# PCB.net
KiCad netlist of a schematic drawn in EAGLE
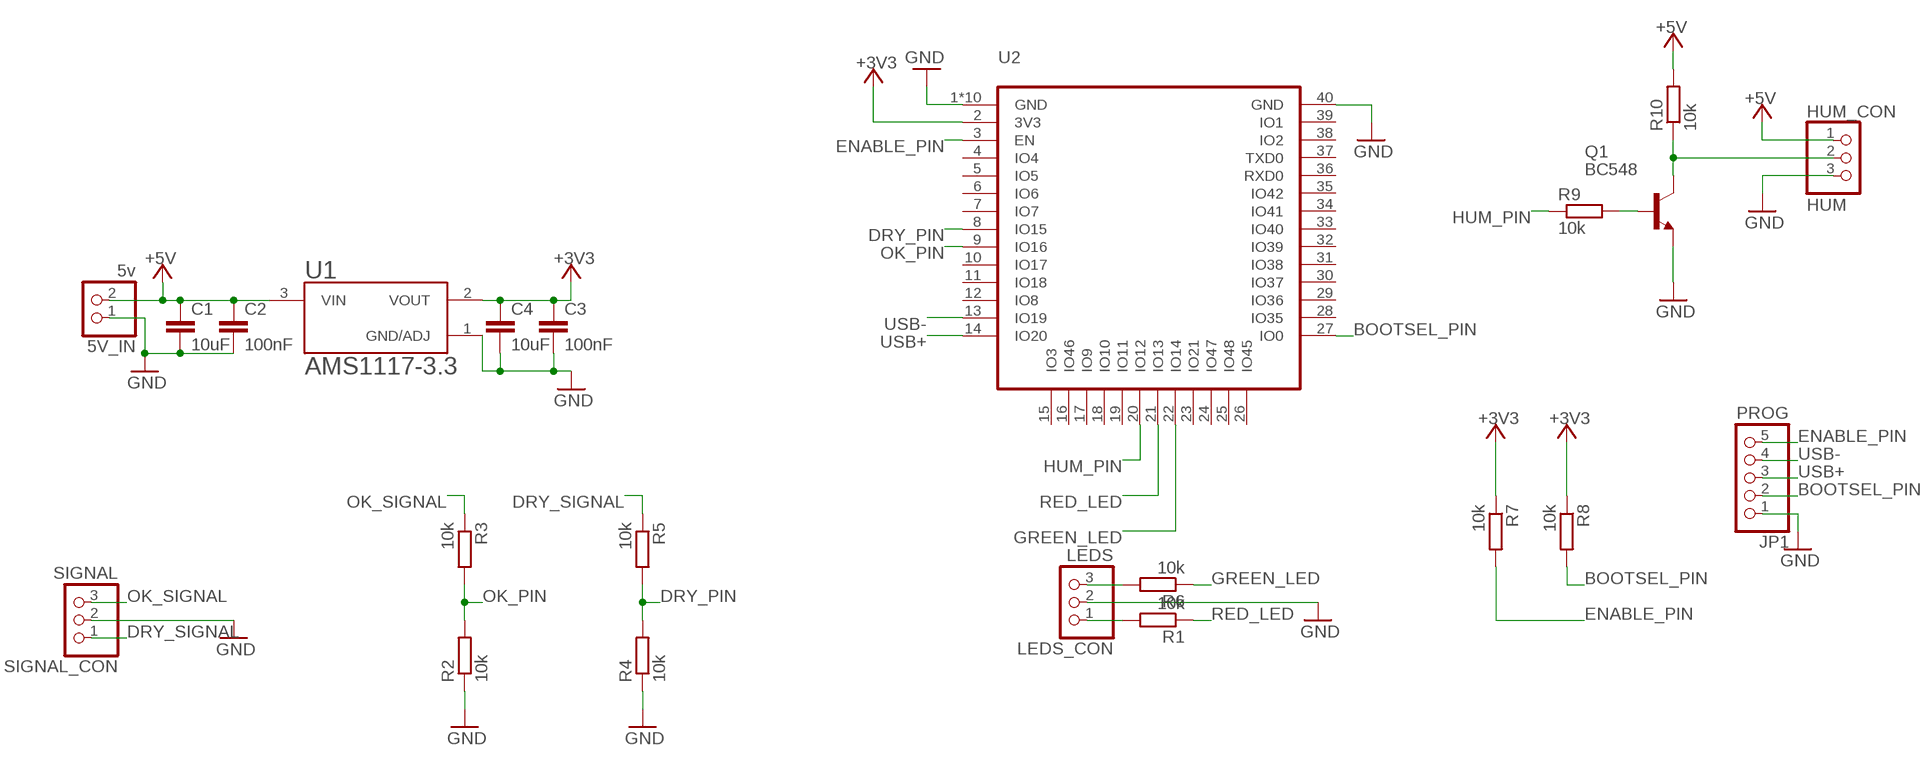
[diagram p0: schematic, sheet 1]

(export (version "E")
  (design (tool "Eeschema 10.0.6"))
  (components
    (comp (ref "5V_IN")
      (value "5v")
      (footprint "eagle-import:1X02")
      (libsource (lib "eagle-import") (part "PINHD-1X2"))
    )
    (comp (ref "C1")
      (value "10uF")
      (footprint "eagle-import:C1206")
      (libsource (lib "eagle-import") (part "C-EUC1206"))
    )
    (comp (ref "C2")
      (value "100nF")
      (footprint "eagle-import:C1206")
      (libsource (lib "eagle-import") (part "C-EUC1206"))
    )
    (comp (ref "C3")
      (value "100nF")
      (footprint "eagle-import:C1206")
      (libsource (lib "eagle-import") (part "C-EUC1206"))
    )
    (comp (ref "C4")
      (value "10uF")
      (footprint "eagle-import:C1206")
      (libsource (lib "eagle-import") (part "C-EUC1206"))
    )
    (comp (ref "HUM_CON")
      (value "HUM")
      (footprint "eagle-import:1X03")
      (libsource (lib "eagle-import") (part "PINHD-1X3"))
    )
    (comp (ref "JP1")
      (value "PROG")
      (footprint "eagle-import:1X05")
      (libsource (lib "eagle-import") (part "PINHD-1X5"))
    )
    (comp (ref "LEDS_CON")
      (value "LEDS")
      (footprint "eagle-import:1X03")
      (libsource (lib "eagle-import") (part "PINHD-1X3"))
    )
    (comp (ref "Q1")
      (value "BC548")
      (footprint "eagle-import:TO92-EBC")
      (libsource (lib "eagle-import") (part "BC548"))
    )
    (comp (ref "R1")
      (value "10k")
      (footprint "eagle-import:R1206")
      (libsource (lib "eagle-import") (part "R-EU_R1206"))
    )
    (comp (ref "R2")
      (value "10k")
      (footprint "eagle-import:R1206")
      (libsource (lib "eagle-import") (part "R-EU_R1206"))
    )
    (comp (ref "R3")
      (value "10k")
      (footprint "eagle-import:R1206")
      (libsource (lib "eagle-import") (part "R-EU_R1206"))
    )
    (comp (ref "R4")
      (value "10k")
      (footprint "eagle-import:R1206")
      (libsource (lib "eagle-import") (part "R-EU_R1206"))
    )
    (comp (ref "R5")
      (value "10k")
      (footprint "eagle-import:R1206")
      (libsource (lib "eagle-import") (part "R-EU_R1206"))
    )
    (comp (ref "R6")
      (value "10k")
      (footprint "eagle-import:R1206")
      (libsource (lib "eagle-import") (part "R-EU_R1206"))
    )
    (comp (ref "R7")
      (value "10k")
      (footprint "eagle-import:R1206")
      (libsource (lib "eagle-import") (part "R-EU_R1206"))
    )
    (comp (ref "R8")
      (value "10k")
      (footprint "eagle-import:R1206")
      (libsource (lib "eagle-import") (part "R-EU_R1206"))
    )
    (comp (ref "R9")
      (value "10k")
      (footprint "eagle-import:R1206")
      (libsource (lib "eagle-import") (part "R-EU_R1206"))
    )
    (comp (ref "R10")
      (value "10k")
      (footprint "eagle-import:R1206")
      (libsource (lib "eagle-import") (part "R-EU_R1206"))
    )
    (comp (ref "SIGNAL_CON")
      (value "SIGNAL")
      (footprint "eagle-import:1X03")
      (libsource (lib "eagle-import") (part "PINHD-1X3"))
    )
    (comp (ref "U1")
      (value "AMS1117-3.3")
      (footprint "eagle-import:SOT229P700X180-4N")
      (fields (field (name "MF") "Advanced Monolithic Systems"))
      (libsource (lib "eagle-import") (part "AMS1117-3.3"))
    )
    (comp (ref "U2")
      (value "ESP32-S3-WROOM-1")
      (footprint "eagle-import:ESP32-S3-WROOM-1")
      (fields (field (name "MF") "Espressif Systems"))
      (libsource (lib "eagle-import") (part "ESP32-S3-WROOM-1"))
    )
  )
  (nets
    (net (code "1") (name "+3V3") (class "Default")
      (node (ref "C3") (pin "1") (pinfunction "1_1") (pintype "passive"))
      (node (ref "C4") (pin "1") (pinfunction "1_1") (pintype "passive"))
      (node (ref "R7") (pin "1") (pinfunction "1_1") (pintype "passive"))
      (node (ref "R8") (pin "1") (pinfunction "1_1") (pintype "passive"))
      (node (ref "U1") (pin "2") (pinfunction "VOUT_2") (pintype "output"))
      (node (ref "U2") (pin "2") (pinfunction "3V3_2") (pintype "bidirectional"))
    )
    (net (code "2") (name "+5V") (class "Default")
      (node (ref "5V_IN") (pin "2") (pinfunction "2_2") (pintype "passive"))
      (node (ref "C1") (pin "1") (pinfunction "1_1") (pintype "passive"))
      (node (ref "C2") (pin "1") (pinfunction "1_1") (pintype "passive"))
      (node (ref "HUM_CON") (pin "1") (pinfunction "1_1") (pintype "passive"))
      (node (ref "R10") (pin "2") (pinfunction "2_2") (pintype "passive"))
      (node (ref "U1") (pin "3") (pinfunction "VIN_3") (pintype "input"))
    )
    (net (code "3") (name "/BOOTSEL_PIN") (class "Default")
      (node (ref "JP1") (pin "2") (pinfunction "2_2") (pintype "passive"))
      (node (ref "R8") (pin "2") (pinfunction "2_2") (pintype "passive"))
      (node (ref "U2") (pin "27") (pinfunction "IO0_27") (pintype "bidirectional"))
    )
    (net (code "4") (name "/DRY_PIN") (class "Default")
      (node (ref "R4") (pin "2") (pinfunction "2_2") (pintype "passive"))
      (node (ref "R5") (pin "2") (pinfunction "2_2") (pintype "passive"))
      (node (ref "U2") (pin "8") (pinfunction "IO15_8") (pintype "bidirectional"))
    )
    (net (code "5") (name "/DRY_SIGNAL") (class "Default")
      (node (ref "R5") (pin "1") (pinfunction "1_1") (pintype "passive"))
      (node (ref "SIGNAL_CON") (pin "1") (pinfunction "1_1") (pintype "passive"))
    )
    (net (code "6") (name "/ENABLE_PIN") (class "Default")
      (node (ref "JP1") (pin "5") (pinfunction "5_5") (pintype "passive"))
      (node (ref "R7") (pin "2") (pinfunction "2_2") (pintype "passive"))
      (node (ref "U2") (pin "3") (pinfunction "EN_3") (pintype "bidirectional"))
    )
    (net (code "7") (name "/GREEN_LED") (class "Default")
      (node (ref "R6") (pin "1") (pinfunction "1_1") (pintype "passive"))
      (node (ref "U2") (pin "22") (pinfunction "IO14_22") (pintype "bidirectional"))
    )
    (net (code "8") (name "/HUM_PIN") (class "Default")
      (node (ref "R9") (pin "1") (pinfunction "1_1") (pintype "passive"))
      (node (ref "U2") (pin "20") (pinfunction "IO12_20") (pintype "bidirectional"))
    )
    (net (code "9") (name "/OK_PIN") (class "Default")
      (node (ref "R2") (pin "2") (pinfunction "2_2") (pintype "passive"))
      (node (ref "R3") (pin "2") (pinfunction "2_2") (pintype "passive"))
      (node (ref "U2") (pin "9") (pinfunction "IO16_9") (pintype "bidirectional"))
    )
    (net (code "10") (name "/OK_SIGNAL") (class "Default")
      (node (ref "R3") (pin "1") (pinfunction "1_1") (pintype "passive"))
      (node (ref "SIGNAL_CON") (pin "3") (pinfunction "3_3") (pintype "passive"))
    )
    (net (code "11") (name "/RED_LED") (class "Default")
      (node (ref "R1") (pin "1") (pinfunction "1_1") (pintype "passive"))
      (node (ref "U2") (pin "21") (pinfunction "IO13_21") (pintype "bidirectional"))
    )
    (net (code "12") (name "/USB+") (class "Default")
      (node (ref "JP1") (pin "3") (pinfunction "3_3") (pintype "passive"))
      (node (ref "U2") (pin "14") (pinfunction "IO20_14") (pintype "bidirectional"))
    )
    (net (code "13") (name "/USB-") (class "Default")
      (node (ref "JP1") (pin "4") (pinfunction "4_4") (pintype "passive"))
      (node (ref "U2") (pin "13") (pinfunction "IO19_13") (pintype "bidirectional"))
    )
    (net (code "14") (name "GND") (class "Default")
      (node (ref "5V_IN") (pin "1") (pinfunction "1_1") (pintype "passive"))
      (node (ref "C1") (pin "2") (pinfunction "2_2") (pintype "passive"))
      (node (ref "C2") (pin "2") (pinfunction "2_2") (pintype "passive"))
      (node (ref "C3") (pin "2") (pinfunction "2_2") (pintype "passive"))
      (node (ref "C4") (pin "2") (pinfunction "2_2") (pintype "passive"))
      (node (ref "HUM_CON") (pin "3") (pinfunction "3_3") (pintype "passive"))
      (node (ref "JP1") (pin "1") (pinfunction "1_1") (pintype "passive"))
      (node (ref "LEDS_CON") (pin "2") (pinfunction "2_2") (pintype "passive"))
      (node (ref "Q1") (pin "E") (pinfunction "E_E") (pintype "passive"))
      (node (ref "R2") (pin "1") (pinfunction "1_1") (pintype "passive"))
      (node (ref "R4") (pin "1") (pinfunction "1_1") (pintype "passive"))
      (node (ref "SIGNAL_CON") (pin "2") (pinfunction "2_2") (pintype "passive"))
      (node (ref "U1") (pin "1") (pinfunction "GND/ADJ_1") (pintype "power_in"))
      (node (ref "U2") (pin "1") (pinfunction "GND_1") (pintype "bidirectional"))
      (node (ref "U2") (pin "40") (pinfunction "GND_40") (pintype "bidirectional"))
      (node (ref "U2") (pin "P$1") (pinfunction "GND_P$1") (pintype "bidirectional"))
      (node (ref "U2") (pin "P$2") (pinfunction "GND_P$2") (pintype "bidirectional"))
      (node (ref "U2") (pin "P$3") (pinfunction "GND_P$3") (pintype "bidirectional"))
      (node (ref "U2") (pin "P$4") (pinfunction "GND_P$4") (pintype "bidirectional"))
      (node (ref "U2") (pin "P$5") (pinfunction "GND_P$5") (pintype "bidirectional"))
      (node (ref "U2") (pin "P$6") (pinfunction "GND_P$6") (pintype "bidirectional"))
      (node (ref "U2") (pin "P$7") (pinfunction "GND_P$7") (pintype "bidirectional"))
      (node (ref "U2") (pin "P$8") (pinfunction "GND_P$8") (pintype "bidirectional"))
      (node (ref "U2") (pin "P$9") (pinfunction "GND_P$9") (pintype "bidirectional"))
    )
    (net (code "15") (name "Net-(HUM_CON-Pad2)") (class "Default")
      (node (ref "HUM_CON") (pin "2") (pinfunction "2_2") (pintype "passive"))
      (node (ref "Q1") (pin "C") (pinfunction "C_C") (pintype "passive"))
      (node (ref "R10") (pin "1") (pinfunction "1_1") (pintype "passive"))
    )
    (net (code "16") (name "Net-(LEDS_CON-Pad1)") (class "Default")
      (node (ref "LEDS_CON") (pin "1") (pinfunction "1_1") (pintype "passive"))
      (node (ref "R1") (pin "2") (pinfunction "2_2") (pintype "passive"))
    )
    (net (code "17") (name "Net-(LEDS_CON-Pad3)") (class "Default")
      (node (ref "LEDS_CON") (pin "3") (pinfunction "3_3") (pintype "passive"))
      (node (ref "R6") (pin "2") (pinfunction "2_2") (pintype "passive"))
    )
    (net (code "18") (name "Net-(Q1-PadB)") (class "Default")
      (node (ref "Q1") (pin "B") (pinfunction "B_B") (pintype "passive"))
      (node (ref "R9") (pin "2") (pinfunction "2_2") (pintype "passive"))
    )
    (net (code "19") (name "unconnected-(U2-IO1-Pad39)") (class "Default")
      (node (ref "U2") (pin "39") (pinfunction "IO1_39") (pintype "bidirectional"))
    )
    (net (code "20") (name "unconnected-(U2-IO2-Pad38)") (class "Default")
      (node (ref "U2") (pin "38") (pinfunction "IO2_38") (pintype "bidirectional"))
    )
    (net (code "21") (name "unconnected-(U2-IO3-Pad15)") (class "Default")
      (node (ref "U2") (pin "15") (pinfunction "IO3_15") (pintype "bidirectional"))
    )
    (net (code "22") (name "unconnected-(U2-IO4-Pad4)") (class "Default")
      (node (ref "U2") (pin "4") (pinfunction "IO4_4") (pintype "bidirectional"))
    )
    (net (code "23") (name "unconnected-(U2-IO5-Pad5)") (class "Default")
      (node (ref "U2") (pin "5") (pinfunction "IO5_5") (pintype "bidirectional"))
    )
    (net (code "24") (name "unconnected-(U2-IO6-Pad6)") (class "Default")
      (node (ref "U2") (pin "6") (pinfunction "IO6_6") (pintype "bidirectional"))
    )
    (net (code "25") (name "unconnected-(U2-IO7-Pad7)") (class "Default")
      (node (ref "U2") (pin "7") (pinfunction "IO7_7") (pintype "bidirectional"))
    )
    (net (code "26") (name "unconnected-(U2-IO8-Pad12)") (class "Default")
      (node (ref "U2") (pin "12") (pinfunction "IO8_12") (pintype "bidirectional"))
    )
    (net (code "27") (name "unconnected-(U2-IO9-Pad17)") (class "Default")
      (node (ref "U2") (pin "17") (pinfunction "IO9_17") (pintype "bidirectional"))
    )
    (net (code "28") (name "unconnected-(U2-IO10-Pad18)") (class "Default")
      (node (ref "U2") (pin "18") (pinfunction "IO10_18") (pintype "bidirectional"))
    )
    (net (code "29") (name "unconnected-(U2-IO11-Pad19)") (class "Default")
      (node (ref "U2") (pin "19") (pinfunction "IO11_19") (pintype "bidirectional"))
    )
    (net (code "30") (name "unconnected-(U2-IO17-Pad10)") (class "Default")
      (node (ref "U2") (pin "10") (pinfunction "IO17_10") (pintype "bidirectional"))
    )
    (net (code "31") (name "unconnected-(U2-IO18-Pad11)") (class "Default")
      (node (ref "U2") (pin "11") (pinfunction "IO18_11") (pintype "bidirectional"))
    )
    (net (code "32") (name "unconnected-(U2-IO21-Pad23)") (class "Default")
      (node (ref "U2") (pin "23") (pinfunction "IO21_23") (pintype "bidirectional"))
    )
    (net (code "33") (name "unconnected-(U2-IO35-Pad28)") (class "Default")
      (node (ref "U2") (pin "28") (pinfunction "IO35_28") (pintype "bidirectional"))
    )
    (net (code "34") (name "unconnected-(U2-IO36-Pad29)") (class "Default")
      (node (ref "U2") (pin "29") (pinfunction "IO36_29") (pintype "bidirectional"))
    )
    (net (code "35") (name "unconnected-(U2-IO37-Pad30)") (class "Default")
      (node (ref "U2") (pin "30") (pinfunction "IO37_30") (pintype "bidirectional"))
    )
    (net (code "36") (name "unconnected-(U2-IO38-Pad31)") (class "Default")
      (node (ref "U2") (pin "31") (pinfunction "IO38_31") (pintype "bidirectional"))
    )
    (net (code "37") (name "unconnected-(U2-IO39-Pad32)") (class "Default")
      (node (ref "U2") (pin "32") (pinfunction "IO39_32") (pintype "bidirectional"))
    )
    (net (code "38") (name "unconnected-(U2-IO40-Pad33)") (class "Default")
      (node (ref "U2") (pin "33") (pinfunction "IO40_33") (pintype "bidirectional"))
    )
    (net (code "39") (name "unconnected-(U2-IO41-Pad34)") (class "Default")
      (node (ref "U2") (pin "34") (pinfunction "IO41_34") (pintype "bidirectional"))
    )
    (net (code "40") (name "unconnected-(U2-IO42-Pad35)") (class "Default")
      (node (ref "U2") (pin "35") (pinfunction "IO42_35") (pintype "bidirectional"))
    )
    (net (code "41") (name "unconnected-(U2-IO45-Pad26)") (class "Default")
      (node (ref "U2") (pin "26") (pinfunction "IO45_26") (pintype "bidirectional"))
    )
    (net (code "42") (name "unconnected-(U2-IO46-Pad16)") (class "Default")
      (node (ref "U2") (pin "16") (pinfunction "IO46_16") (pintype "bidirectional"))
    )
    (net (code "43") (name "unconnected-(U2-IO47-Pad24)") (class "Default")
      (node (ref "U2") (pin "24") (pinfunction "IO47_24") (pintype "bidirectional"))
    )
    (net (code "44") (name "unconnected-(U2-IO48-Pad25)") (class "Default")
      (node (ref "U2") (pin "25") (pinfunction "IO48_25") (pintype "bidirectional"))
    )
    (net (code "45") (name "unconnected-(U2-RXD0-Pad36)") (class "Default")
      (node (ref "U2") (pin "36") (pinfunction "RXD0_36") (pintype "bidirectional"))
    )
    (net (code "46") (name "unconnected-(U2-TXD0-Pad37)") (class "Default")
      (node (ref "U2") (pin "37") (pinfunction "TXD0_37") (pintype "bidirectional"))
    )
  )
)
